# ProPrj_NFC_Buisness_card_2026-06-10_16-3.net
KiCad netlist of a schematic drawn in EasyEDA Pro
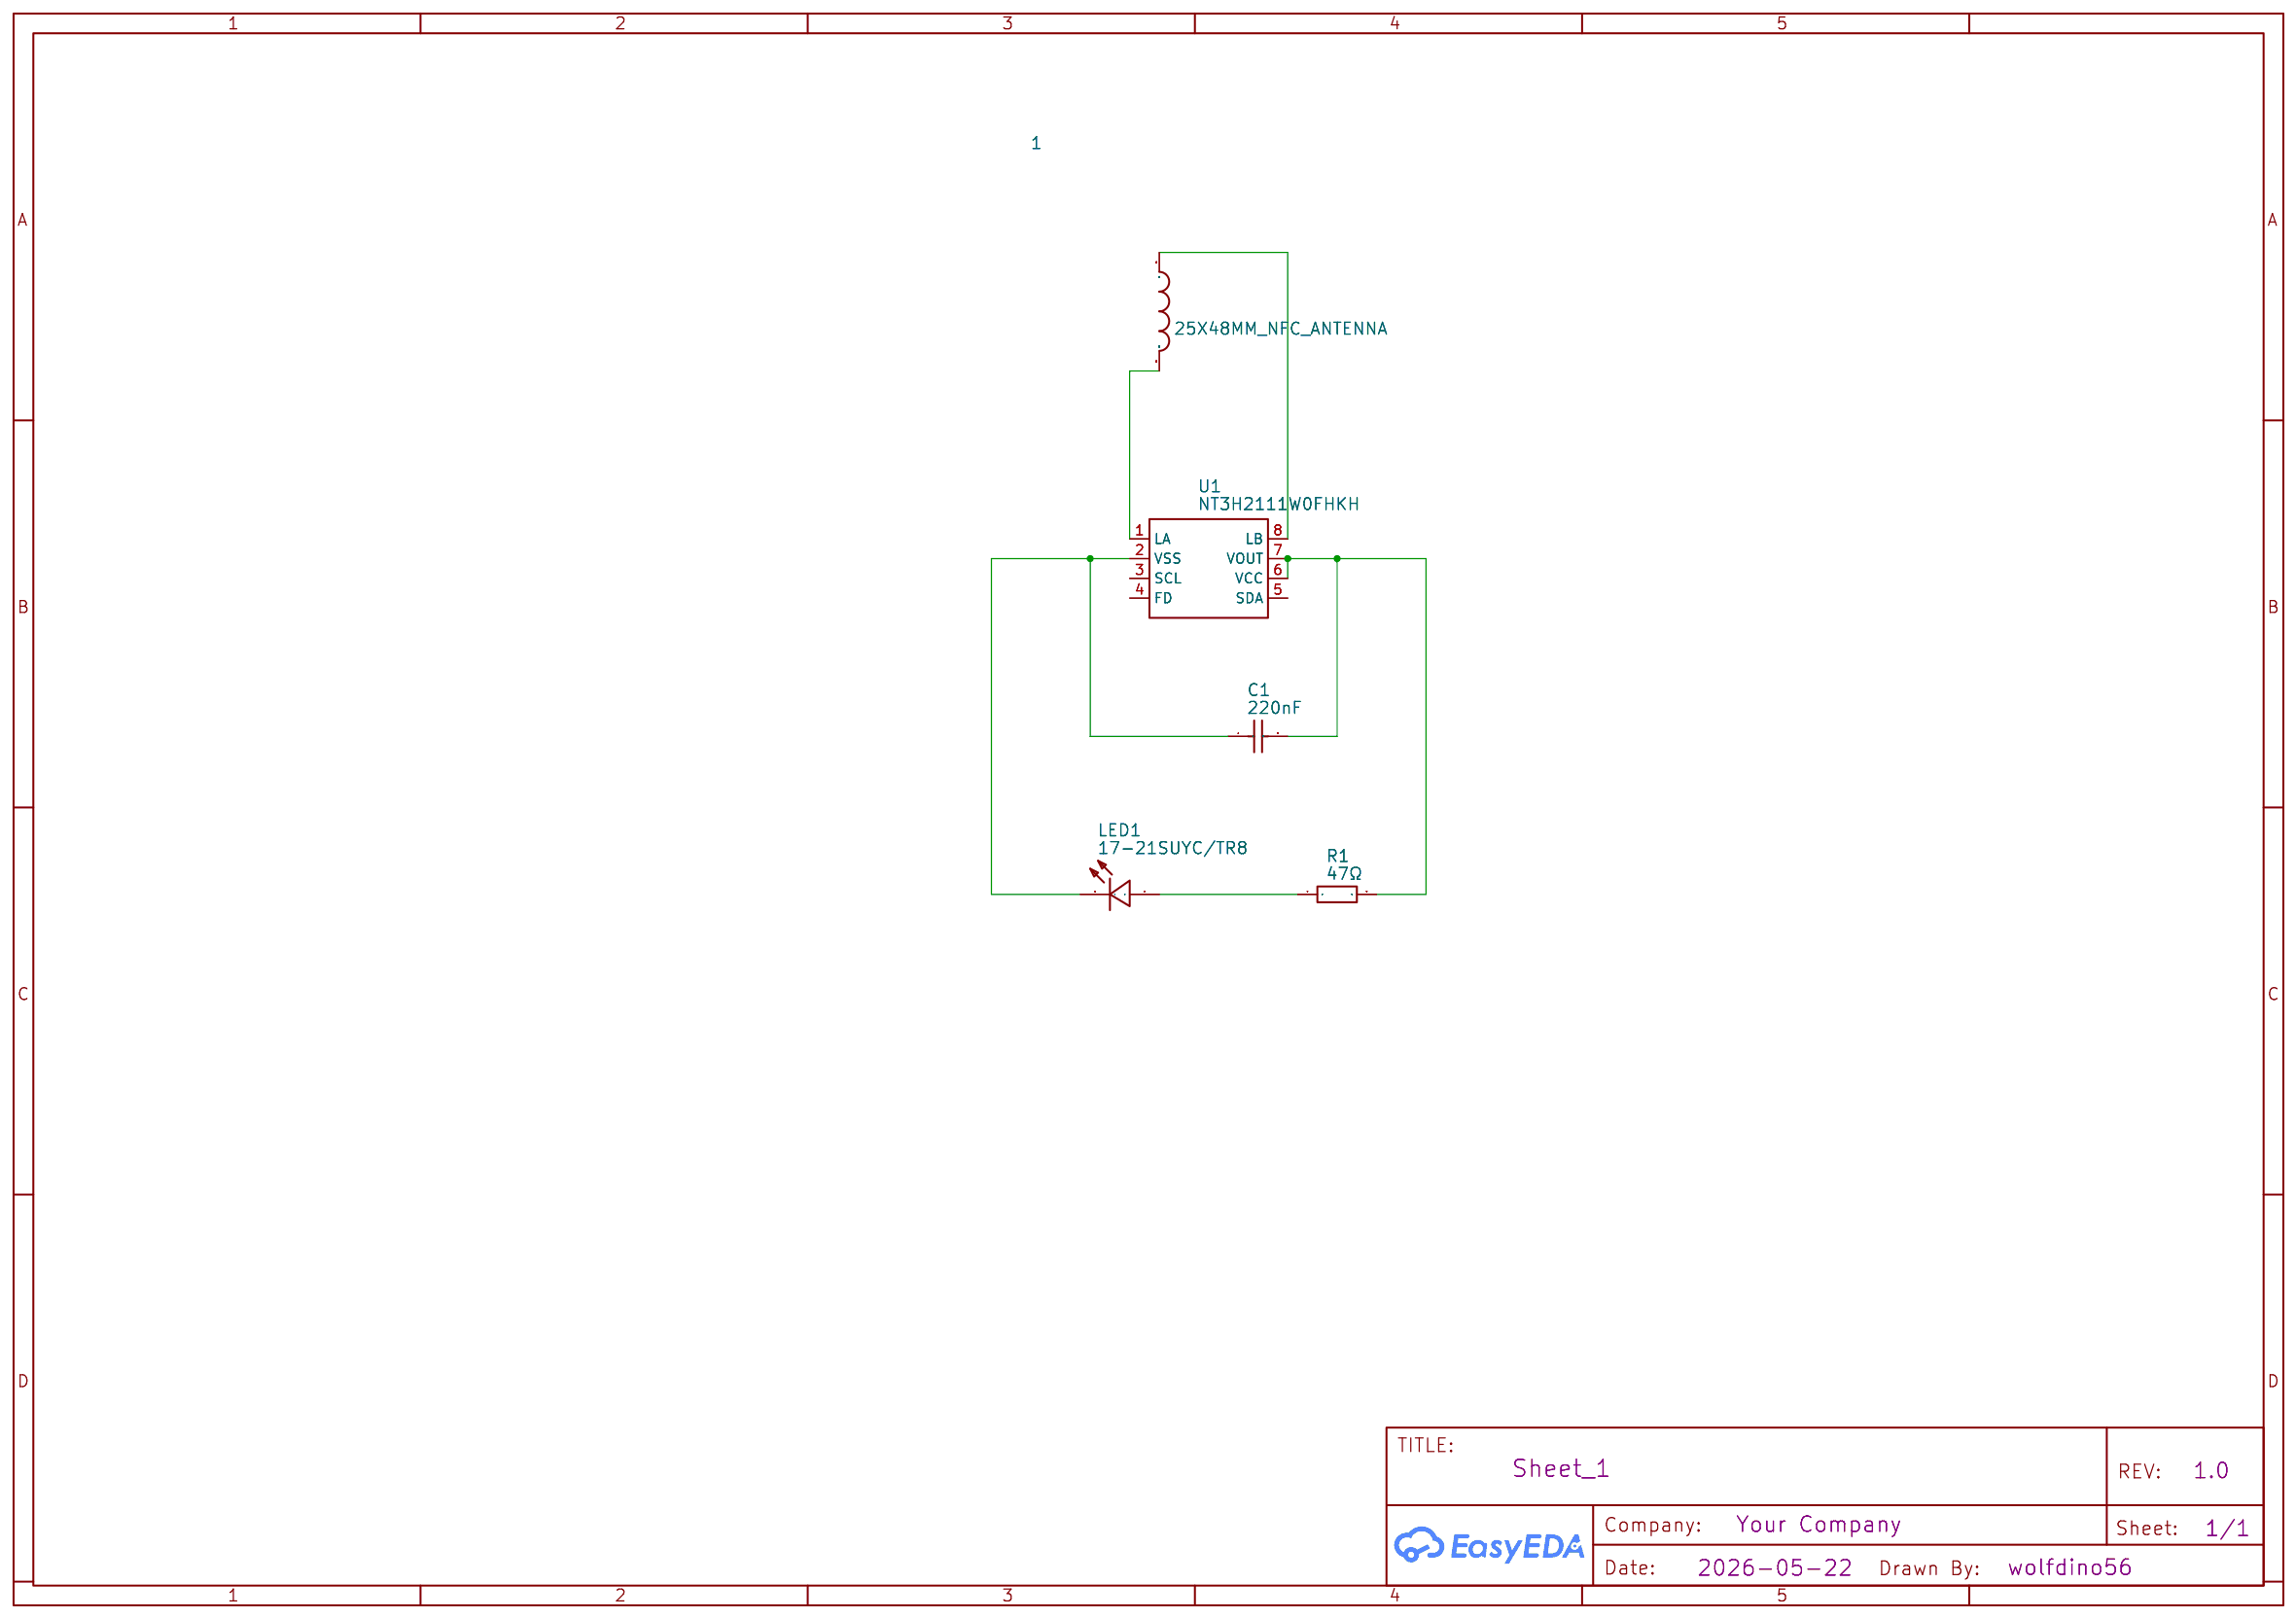
[diagram p0: schematic sheet]

(export (version "E")
  (design (tool "Eeschema 10.0.6"))
  (components
    (comp (ref "1")
      (value "25X48MM_NFC_ANTENNA")
      (footprint "easyedapro:25X48MM_NFC_ANTENNA")
      (libsource (lib "easyedapro") (part "25X48MM_NFC_ANTENNA"))
    )
    (comp (ref "C1")
      (value "220nF")
      (footprint "easyedapro:C0603")
      (fields
        (field (name "Manufacturer Part") "CL10B224KA8NNNC")
        (field (name "Manufacturer") "SAMSUNG(三星)")
      )
      (libsource (lib "easyedapro") (part "220nF"))
    )
    (comp (ref "LED1")
      (value "17-21SUYC/TR8")
      (footprint "easyedapro:LED0805-R-RD")
      (fields (field (name "Manufacturer Part") "KT-0805黄灯") (field (name "Manufacturer") "KENTO"))
      (libsource (lib "easyedapro") (part "17-21SUYC/TR8"))
    )
    (comp (ref "R1")
      (value "47Ω")
      (footprint "easyedapro:R0603")
      (fields
        (field (name "Manufacturer Part") "0603WAF470JT5E")
        (field (name "Manufacturer") "UNI-ROYAL(厚声)")
      )
      (libsource (lib "easyedapro") (part "47Ω"))
    )
    (comp (ref "U1")
      (value "NT3H2111W0FHKH")
      (footprint "easyedapro:XQFN-8_L1.6-W1.6-P0.50-BL_NT3H2111W0FHKH")
      (fields (field (name "Manufacturer") "NXP(恩智浦)"))
      (libsource (lib "easyedapro") (part "NT3H2111W0FHKH"))
    )
  )
  (nets
    (net (code "1") (name "Net-(LED1-+)") (class "Default")
      (node (ref "LED1") (pin "1") (pinfunction "+_1") (pintype "unspecified"))
      (node (ref "R1") (pin "1") (pinfunction "1_1") (pintype "input"))
    )
    (net (code "2") (name "Net-(LED1--)") (class "Default")
      (node (ref "C1") (pin "1") (pinfunction "1_1") (pintype "input"))
      (node (ref "LED1") (pin "2") (pinfunction "-_2") (pintype "unspecified"))
      (node (ref "U1") (pin "2") (pinfunction "VSS_2") (pintype "unspecified"))
    )
    (net (code "3") (name "Net-(U1-LA)") (class "Default")
      (node (ref "1") (pin "P$2") (pinfunction "P$2_P$2") (pintype "bidirectional"))
      (node (ref "U1") (pin "1") (pinfunction "LA_1") (pintype "unspecified"))
    )
    (net (code "4") (name "Net-(U1-LB)") (class "Default")
      (node (ref "1") (pin "P$1") (pinfunction "P$1_P$1") (pintype "bidirectional"))
      (node (ref "U1") (pin "8") (pinfunction "LB_8") (pintype "unspecified"))
    )
    (net (code "5") (name "Net-(U1-VCC)") (class "Default")
      (node (ref "C1") (pin "2") (pinfunction "2_2") (pintype "input"))
      (node (ref "R1") (pin "2") (pinfunction "2_2") (pintype "input"))
      (node (ref "U1") (pin "6") (pinfunction "VCC_6") (pintype "unspecified"))
      (node (ref "U1") (pin "7") (pinfunction "VOUT_7") (pintype "unspecified"))
    )
    (net (code "6") (name "unconnected-(U1-FD-Pad4)") (class "Default")
      (node (ref "U1") (pin "4") (pinfunction "FD_4") (pintype "unspecified"))
    )
    (net (code "7") (name "unconnected-(U1-SCL-Pad3)") (class "Default")
      (node (ref "U1") (pin "3") (pinfunction "SCL_3") (pintype "unspecified"))
    )
    (net (code "8") (name "unconnected-(U1-SDA-Pad5)") (class "Default")
      (node (ref "U1") (pin "5") (pinfunction "SDA_5") (pintype "unspecified"))
    )
  )
)
